# ambient_rpi_shield.net
KiCad netlist of a schematic drawn in EAGLE
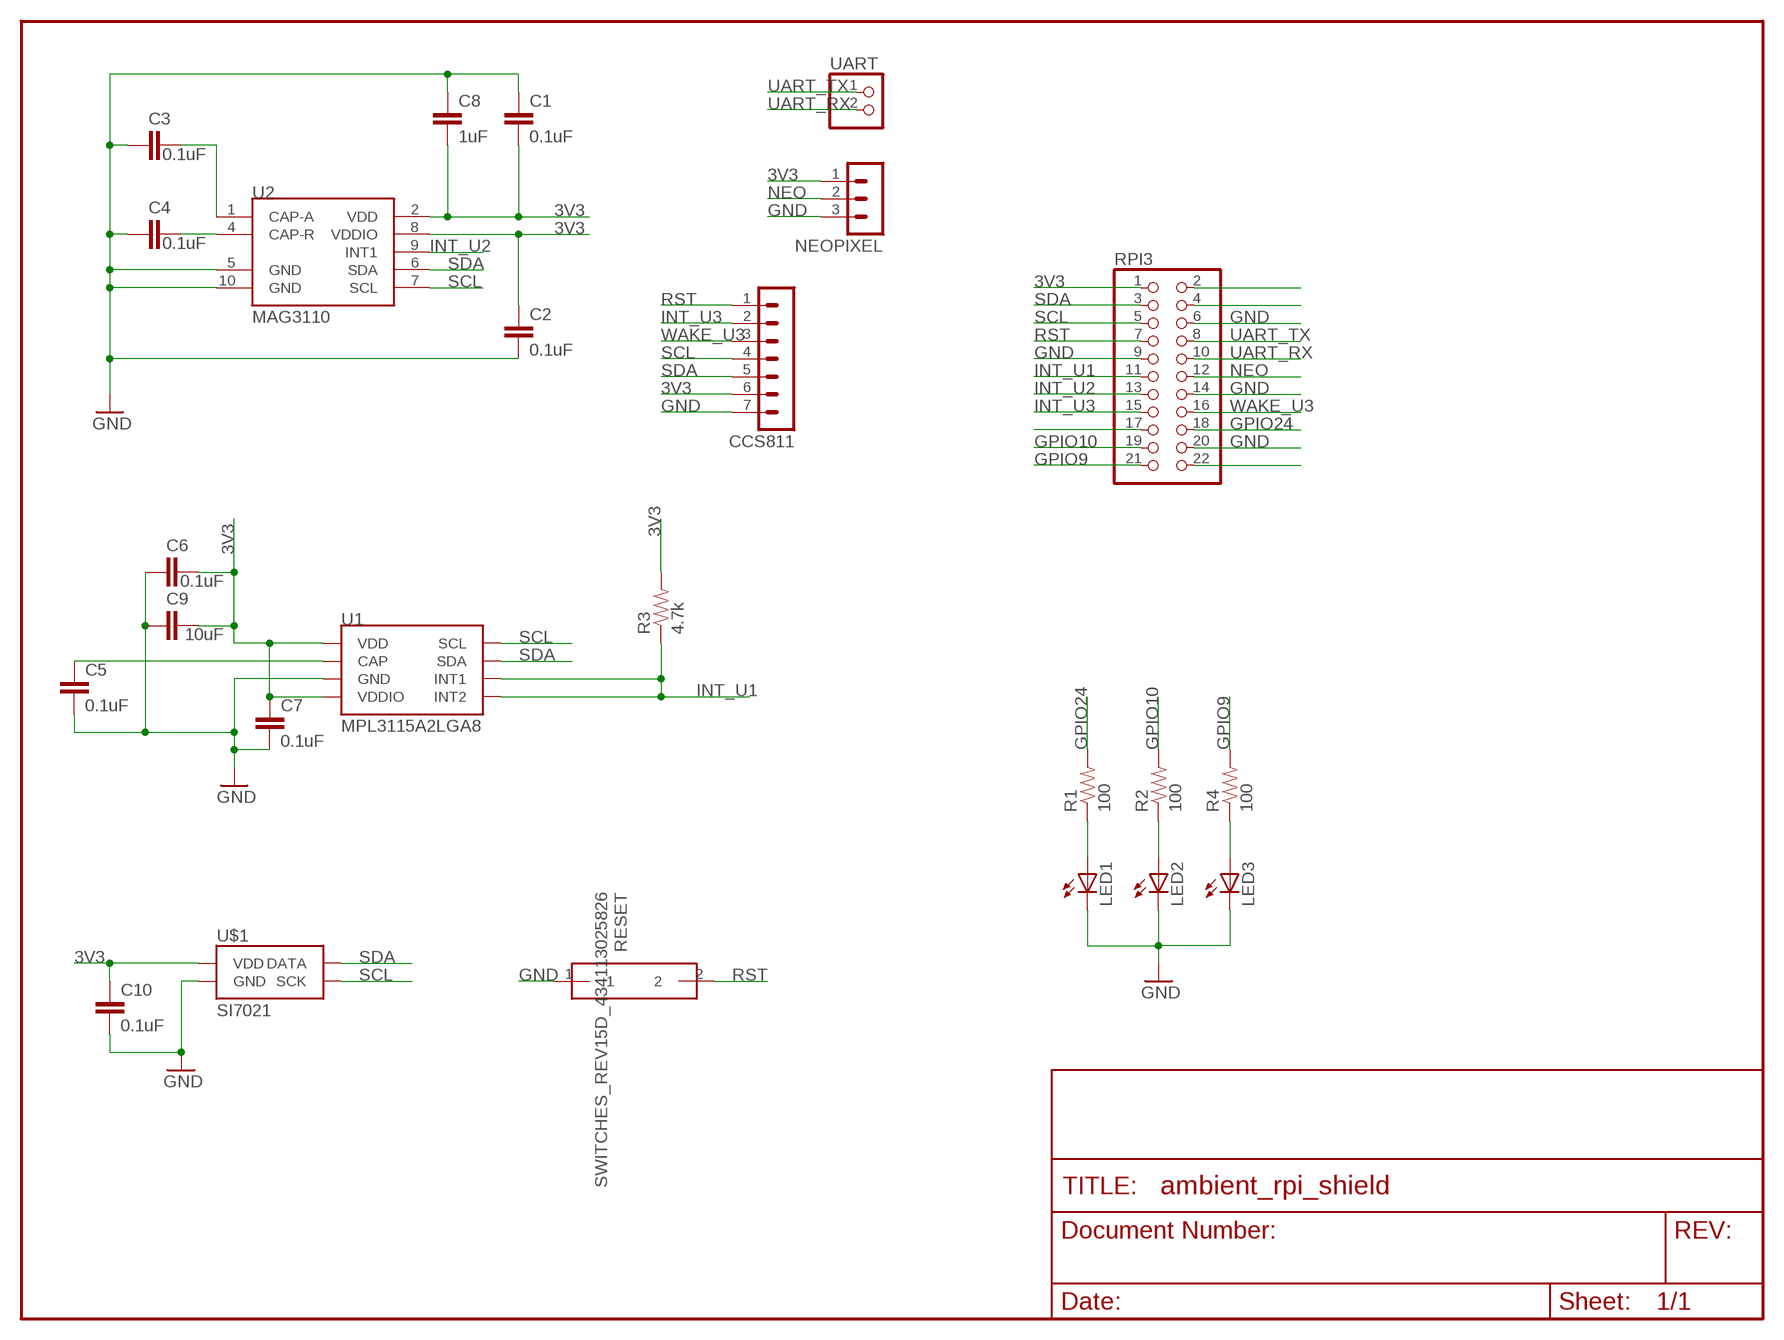
[diagram p0: schematic, sheet 1]

(export (version "E")
  (design (tool "Eeschema 10.0.6"))
  (components
    (comp (ref "C1")
      (value "0.1uF")
      (footprint "eagle-import:0603-CAP")
      (libsource (lib "eagle-import") (part "CAP0603-CAP"))
    )
    (comp (ref "C2")
      (value "0.1uF")
      (footprint "eagle-import:0603-CAP")
      (libsource (lib "eagle-import") (part "CAP0603-CAP"))
    )
    (comp (ref "C3")
      (value "0.1uF")
      (footprint "eagle-import:0603-CAP")
      (libsource (lib "eagle-import") (part "CAP0603-CAP"))
    )
    (comp (ref "C4")
      (value "0.1uF")
      (footprint "eagle-import:0603-CAP")
      (libsource (lib "eagle-import") (part "CAP0603-CAP"))
    )
    (comp (ref "C5")
      (value "0.1uF")
      (footprint "eagle-import:0603-CAP")
      (libsource (lib "eagle-import") (part "CAP0603-CAP"))
    )
    (comp (ref "C6")
      (value "0.1uF")
      (footprint "eagle-import:0603-CAP")
      (libsource (lib "eagle-import") (part "CAP0603-CAP"))
    )
    (comp (ref "C7")
      (value "0.1uF")
      (footprint "eagle-import:0603-CAP")
      (libsource (lib "eagle-import") (part "CAP0603-CAP"))
    )
    (comp (ref "C8")
      (value "1uF")
      (footprint "eagle-import:0603-CAP")
      (libsource (lib "eagle-import") (part "CAP0603-CAP"))
    )
    (comp (ref "C9")
      (value "10uF")
      (footprint "eagle-import:0603-CAP")
      (libsource (lib "eagle-import") (part "CAP0603-CAP"))
    )
    (comp (ref "C10")
      (value "0.1uF")
      (footprint "eagle-import:0603-CAP")
      (libsource (lib "eagle-import") (part "CAP0603-CAP"))
    )
    (comp (ref "CCS811")
      (value "MA07-1")
      (footprint "eagle-import:MA07-1")
      (libsource (lib "eagle-import") (part "MA07-1"))
    )
    (comp (ref "LED1")
      (value "LED_LEDCHIP-LED0805")
      (footprint "eagle-import:LED_CHIP-LED0805")
      (libsource (lib "eagle-import") (part "LED_LEDCHIP-LED0805"))
    )
    (comp (ref "LED2")
      (value "LED_LEDCHIP-LED0805")
      (footprint "eagle-import:LED_CHIP-LED0805")
      (libsource (lib "eagle-import") (part "LED_LEDCHIP-LED0805"))
    )
    (comp (ref "LED3")
      (value "LED_LEDCHIP-LED0603")
      (footprint "eagle-import:LED_CHIP-LED0603")
      (libsource (lib "eagle-import") (part "LED_LEDCHIP-LED0603"))
    )
    (comp (ref "NEOPIXEL")
      (value "MA03-1")
      (footprint "eagle-import:MA03-1")
      (libsource (lib "eagle-import") (part "MA03-1"))
    )
    (comp (ref "R1")
      (value "100")
      (footprint "eagle-import:SPARKFUN_0603-RES")
      (libsource (lib "eagle-import") (part "SPARKFUN_RESISTOR0603-RES"))
    )
    (comp (ref "R2")
      (value "100")
      (footprint "eagle-import:SPARKFUN_0603-RES")
      (libsource (lib "eagle-import") (part "SPARKFUN_RESISTOR0603-RES"))
    )
    (comp (ref "R3")
      (value "4.7k")
      (footprint "eagle-import:0603-RES")
      (libsource (lib "eagle-import") (part "RESISTOR0603-RES"))
    )
    (comp (ref "R4")
      (value "100")
      (footprint "eagle-import:SPARKFUN_0603-RES")
      (libsource (lib "eagle-import") (part "SPARKFUN_RESISTOR0603-RES"))
    )
    (comp (ref "RESET")
      (value "SWITCHES_REV15D_434113025826")
      (footprint "eagle-import:SWITCHES_REV15D_434113025826")
      (libsource (lib "eagle-import") (part "SWITCHES_REV15D_434113025826"))
    )
    (comp (ref "RPI3")
      (value "PINHD-2X11")
      (footprint "eagle-import:2X11")
      (libsource (lib "eagle-import") (part "PINHD-2X11"))
    )
    (comp (ref "U$1")
      (value "SI7021")
      (footprint "eagle-import:SI7021")
      (libsource (lib "eagle-import") (part "SI7021"))
    )
    (comp (ref "U1")
      (value "MPL3115A2LGA8")
      (footprint "eagle-import:LGA8")
      (libsource (lib "eagle-import") (part "MPL3115A2LGA8"))
    )
    (comp (ref "U2")
      (value "MAG3110")
      (footprint "eagle-import:DFN-10")
      (libsource (lib "eagle-import") (part "MAG3110"))
    )
    (comp (ref "UART")
      (value "PINHD-1X2")
      (footprint "eagle-import:1X02")
      (libsource (lib "eagle-import") (part "PINHD-1X2"))
    )
  )
  (nets
    (net (code "1") (name "/3V3") (class "Default")
      (node (ref "C1") (pin "2") (pinfunction "2_2") (pintype "passive"))
      (node (ref "C10") (pin "1") (pinfunction "1_1") (pintype "passive"))
      (node (ref "C2") (pin "1") (pinfunction "1_1") (pintype "passive"))
      (node (ref "C6") (pin "2") (pinfunction "2_2") (pintype "passive"))
      (node (ref "C7") (pin "1") (pinfunction "1_1") (pintype "passive"))
      (node (ref "C8") (pin "2") (pinfunction "2_2") (pintype "passive"))
      (node (ref "C9") (pin "2") (pinfunction "2_2") (pintype "passive"))
      (node (ref "CCS811") (pin "6") (pinfunction "6_6") (pintype "passive"))
      (node (ref "NEOPIXEL") (pin "1") (pinfunction "1_1") (pintype "passive"))
      (node (ref "R3") (pin "2") (pinfunction "2_2") (pintype "passive"))
      (node (ref "RPI3") (pin "1") (pinfunction "1_1") (pintype "passive"))
      (node (ref "U$1") (pin "VDD") (pinfunction "VDD_VDD") (pintype "power_in"))
      (node (ref "U1") (pin "1") (pinfunction "VDD_1") (pintype "power_in"))
      (node (ref "U1") (pin "4") (pinfunction "VDDIO_4") (pintype "power_in"))
      (node (ref "U2") (pin "2") (pinfunction "VDD_2") (pintype "bidirectional"))
      (node (ref "U2") (pin "8") (pinfunction "VDDIO_8") (pintype "bidirectional"))
    )
    (net (code "2") (name "/GPIO9") (class "Default")
      (node (ref "R4") (pin "2") (pinfunction "2_2") (pintype "passive"))
      (node (ref "RPI3") (pin "21") (pinfunction "21_21") (pintype "passive"))
    )
    (net (code "3") (name "/GPIO10") (class "Default")
      (node (ref "R2") (pin "2") (pinfunction "2_2") (pintype "passive"))
      (node (ref "RPI3") (pin "19") (pinfunction "19_19") (pintype "passive"))
    )
    (net (code "4") (name "/GPIO24") (class "Default")
      (node (ref "R1") (pin "2") (pinfunction "2_2") (pintype "passive"))
      (node (ref "RPI3") (pin "18") (pinfunction "18_18") (pintype "passive"))
    )
    (net (code "5") (name "/INT_U1") (class "Default")
      (node (ref "R3") (pin "1") (pinfunction "1_1") (pintype "passive"))
      (node (ref "RPI3") (pin "11") (pinfunction "11_11") (pintype "passive"))
      (node (ref "U1") (pin "5") (pinfunction "INT2_5") (pintype "output"))
      (node (ref "U1") (pin "6") (pinfunction "INT1_6") (pintype "output"))
    )
    (net (code "6") (name "/INT_U2") (class "Default")
      (node (ref "RPI3") (pin "13") (pinfunction "13_13") (pintype "passive"))
      (node (ref "U2") (pin "9") (pinfunction "INT1_9") (pintype "bidirectional"))
    )
    (net (code "7") (name "/INT_U3") (class "Default")
      (node (ref "CCS811") (pin "2") (pinfunction "2_2") (pintype "passive"))
      (node (ref "RPI3") (pin "15") (pinfunction "15_15") (pintype "passive"))
    )
    (net (code "8") (name "/NEO") (class "Default")
      (node (ref "NEOPIXEL") (pin "2") (pinfunction "2_2") (pintype "passive"))
      (node (ref "RPI3") (pin "12") (pinfunction "12_12") (pintype "passive"))
    )
    (net (code "9") (name "/RST") (class "Default")
      (node (ref "CCS811") (pin "1") (pinfunction "1_1") (pintype "passive"))
      (node (ref "RESET") (pin "2") (pinfunction "2_2") (pintype "bidirectional"))
      (node (ref "RPI3") (pin "7") (pinfunction "7_7") (pintype "passive"))
    )
    (net (code "10") (name "/SCL") (class "Default")
      (node (ref "CCS811") (pin "4") (pinfunction "4_4") (pintype "passive"))
      (node (ref "RPI3") (pin "5") (pinfunction "5_5") (pintype "passive"))
      (node (ref "U$1") (pin "SCK") (pinfunction "SCK_SCK") (pintype "input"))
      (node (ref "U1") (pin "8") (pinfunction "SCL_8") (pintype "bidirectional"))
      (node (ref "U2") (pin "7") (pinfunction "SCL_7") (pintype "bidirectional"))
    )
    (net (code "11") (name "/SDA") (class "Default")
      (node (ref "CCS811") (pin "5") (pinfunction "5_5") (pintype "passive"))
      (node (ref "RPI3") (pin "3") (pinfunction "3_3") (pintype "passive"))
      (node (ref "U$1") (pin "DATA") (pinfunction "DATA_DATA") (pintype "bidirectional"))
      (node (ref "U1") (pin "7") (pinfunction "SDA_7") (pintype "bidirectional"))
      (node (ref "U2") (pin "6") (pinfunction "SDA_6") (pintype "bidirectional"))
    )
    (net (code "12") (name "/UART_RX") (class "Default")
      (node (ref "RPI3") (pin "10") (pinfunction "10_10") (pintype "passive"))
      (node (ref "UART") (pin "2") (pinfunction "2_2") (pintype "passive"))
    )
    (net (code "13") (name "/UART_TX") (class "Default")
      (node (ref "RPI3") (pin "8") (pinfunction "8_8") (pintype "passive"))
      (node (ref "UART") (pin "1") (pinfunction "1_1") (pintype "passive"))
    )
    (net (code "14") (name "/WAKE_U3") (class "Default")
      (node (ref "CCS811") (pin "3") (pinfunction "3_3") (pintype "passive"))
      (node (ref "RPI3") (pin "16") (pinfunction "16_16") (pintype "passive"))
    )
    (net (code "15") (name "GND") (class "Default")
      (node (ref "C1") (pin "1") (pinfunction "1_1") (pintype "passive"))
      (node (ref "C10") (pin "2") (pinfunction "2_2") (pintype "passive"))
      (node (ref "C2") (pin "2") (pinfunction "2_2") (pintype "passive"))
      (node (ref "C3") (pin "1") (pinfunction "1_1") (pintype "passive"))
      (node (ref "C4") (pin "1") (pinfunction "1_1") (pintype "passive"))
      (node (ref "C5") (pin "2") (pinfunction "2_2") (pintype "passive"))
      (node (ref "C6") (pin "1") (pinfunction "1_1") (pintype "passive"))
      (node (ref "C7") (pin "2") (pinfunction "2_2") (pintype "passive"))
      (node (ref "C8") (pin "1") (pinfunction "1_1") (pintype "passive"))
      (node (ref "C9") (pin "1") (pinfunction "1_1") (pintype "passive"))
      (node (ref "CCS811") (pin "7") (pinfunction "7_7") (pintype "passive"))
      (node (ref "LED1") (pin "C") (pinfunction "C_C") (pintype "passive"))
      (node (ref "LED2") (pin "C") (pinfunction "C_C") (pintype "passive"))
      (node (ref "LED3") (pin "C") (pinfunction "C_C") (pintype "passive"))
      (node (ref "NEOPIXEL") (pin "3") (pinfunction "3_3") (pintype "passive"))
      (node (ref "RESET") (pin "1") (pinfunction "1_1") (pintype "bidirectional"))
      (node (ref "RPI3") (pin "14") (pinfunction "14_14") (pintype "passive"))
      (node (ref "RPI3") (pin "20") (pinfunction "20_20") (pintype "passive"))
      (node (ref "RPI3") (pin "6") (pinfunction "6_6") (pintype "passive"))
      (node (ref "RPI3") (pin "9") (pinfunction "9_9") (pintype "passive"))
      (node (ref "U$1") (pin "GND") (pinfunction "GND_GND") (pintype "power_in"))
      (node (ref "U1") (pin "3") (pinfunction "GND_3") (pintype "power_in"))
      (node (ref "U2") (pin "10") (pinfunction "GND_10") (pintype "bidirectional"))
      (node (ref "U2") (pin "5") (pinfunction "GND_5") (pintype "bidirectional"))
    )
    (net (code "16") (name "Net-(LED1-PadA)") (class "Default")
      (node (ref "LED1") (pin "A") (pinfunction "A_A") (pintype "passive"))
      (node (ref "R1") (pin "1") (pinfunction "1_1") (pintype "passive"))
    )
    (net (code "17") (name "Net-(LED2-PadA)") (class "Default")
      (node (ref "LED2") (pin "A") (pinfunction "A_A") (pintype "passive"))
      (node (ref "R2") (pin "1") (pinfunction "1_1") (pintype "passive"))
    )
    (net (code "18") (name "Net-(LED3-PadA)") (class "Default")
      (node (ref "LED3") (pin "A") (pinfunction "A_A") (pintype "passive"))
      (node (ref "R4") (pin "1") (pinfunction "1_1") (pintype "passive"))
    )
    (net (code "19") (name "Net-(U1-CAP)") (class "Default")
      (node (ref "C5") (pin "1") (pinfunction "1_1") (pintype "passive"))
      (node (ref "U1") (pin "2") (pinfunction "CAP_2") (pintype "power_in"))
    )
    (net (code "20") (name "Net-(U2-CAP-A)") (class "Default")
      (node (ref "C3") (pin "2") (pinfunction "2_2") (pintype "passive"))
      (node (ref "U2") (pin "1") (pinfunction "CAP-A_1") (pintype "bidirectional"))
    )
    (net (code "21") (name "Net-(U2-CAP-R)") (class "Default")
      (node (ref "C4") (pin "2") (pinfunction "2_2") (pintype "passive"))
      (node (ref "U2") (pin "4") (pinfunction "CAP-R_4") (pintype "bidirectional"))
    )
    (net (code "22") (name "unconnected-(RPI3-Pad2)") (class "Default")
      (node (ref "RPI3") (pin "2") (pinfunction "2_2") (pintype "passive"))
    )
    (net (code "23") (name "unconnected-(RPI3-Pad4)") (class "Default")
      (node (ref "RPI3") (pin "4") (pinfunction "4_4") (pintype "passive"))
    )
    (net (code "24") (name "unconnected-(RPI3-Pad17)") (class "Default")
      (node (ref "RPI3") (pin "17") (pinfunction "17_17") (pintype "passive"))
    )
    (net (code "25") (name "unconnected-(RPI3-Pad22)") (class "Default")
      (node (ref "RPI3") (pin "22") (pinfunction "22_22") (pintype "passive"))
    )
  )
)
